# top.net
KiCad netlist of a schematic drawn in Altium Designer
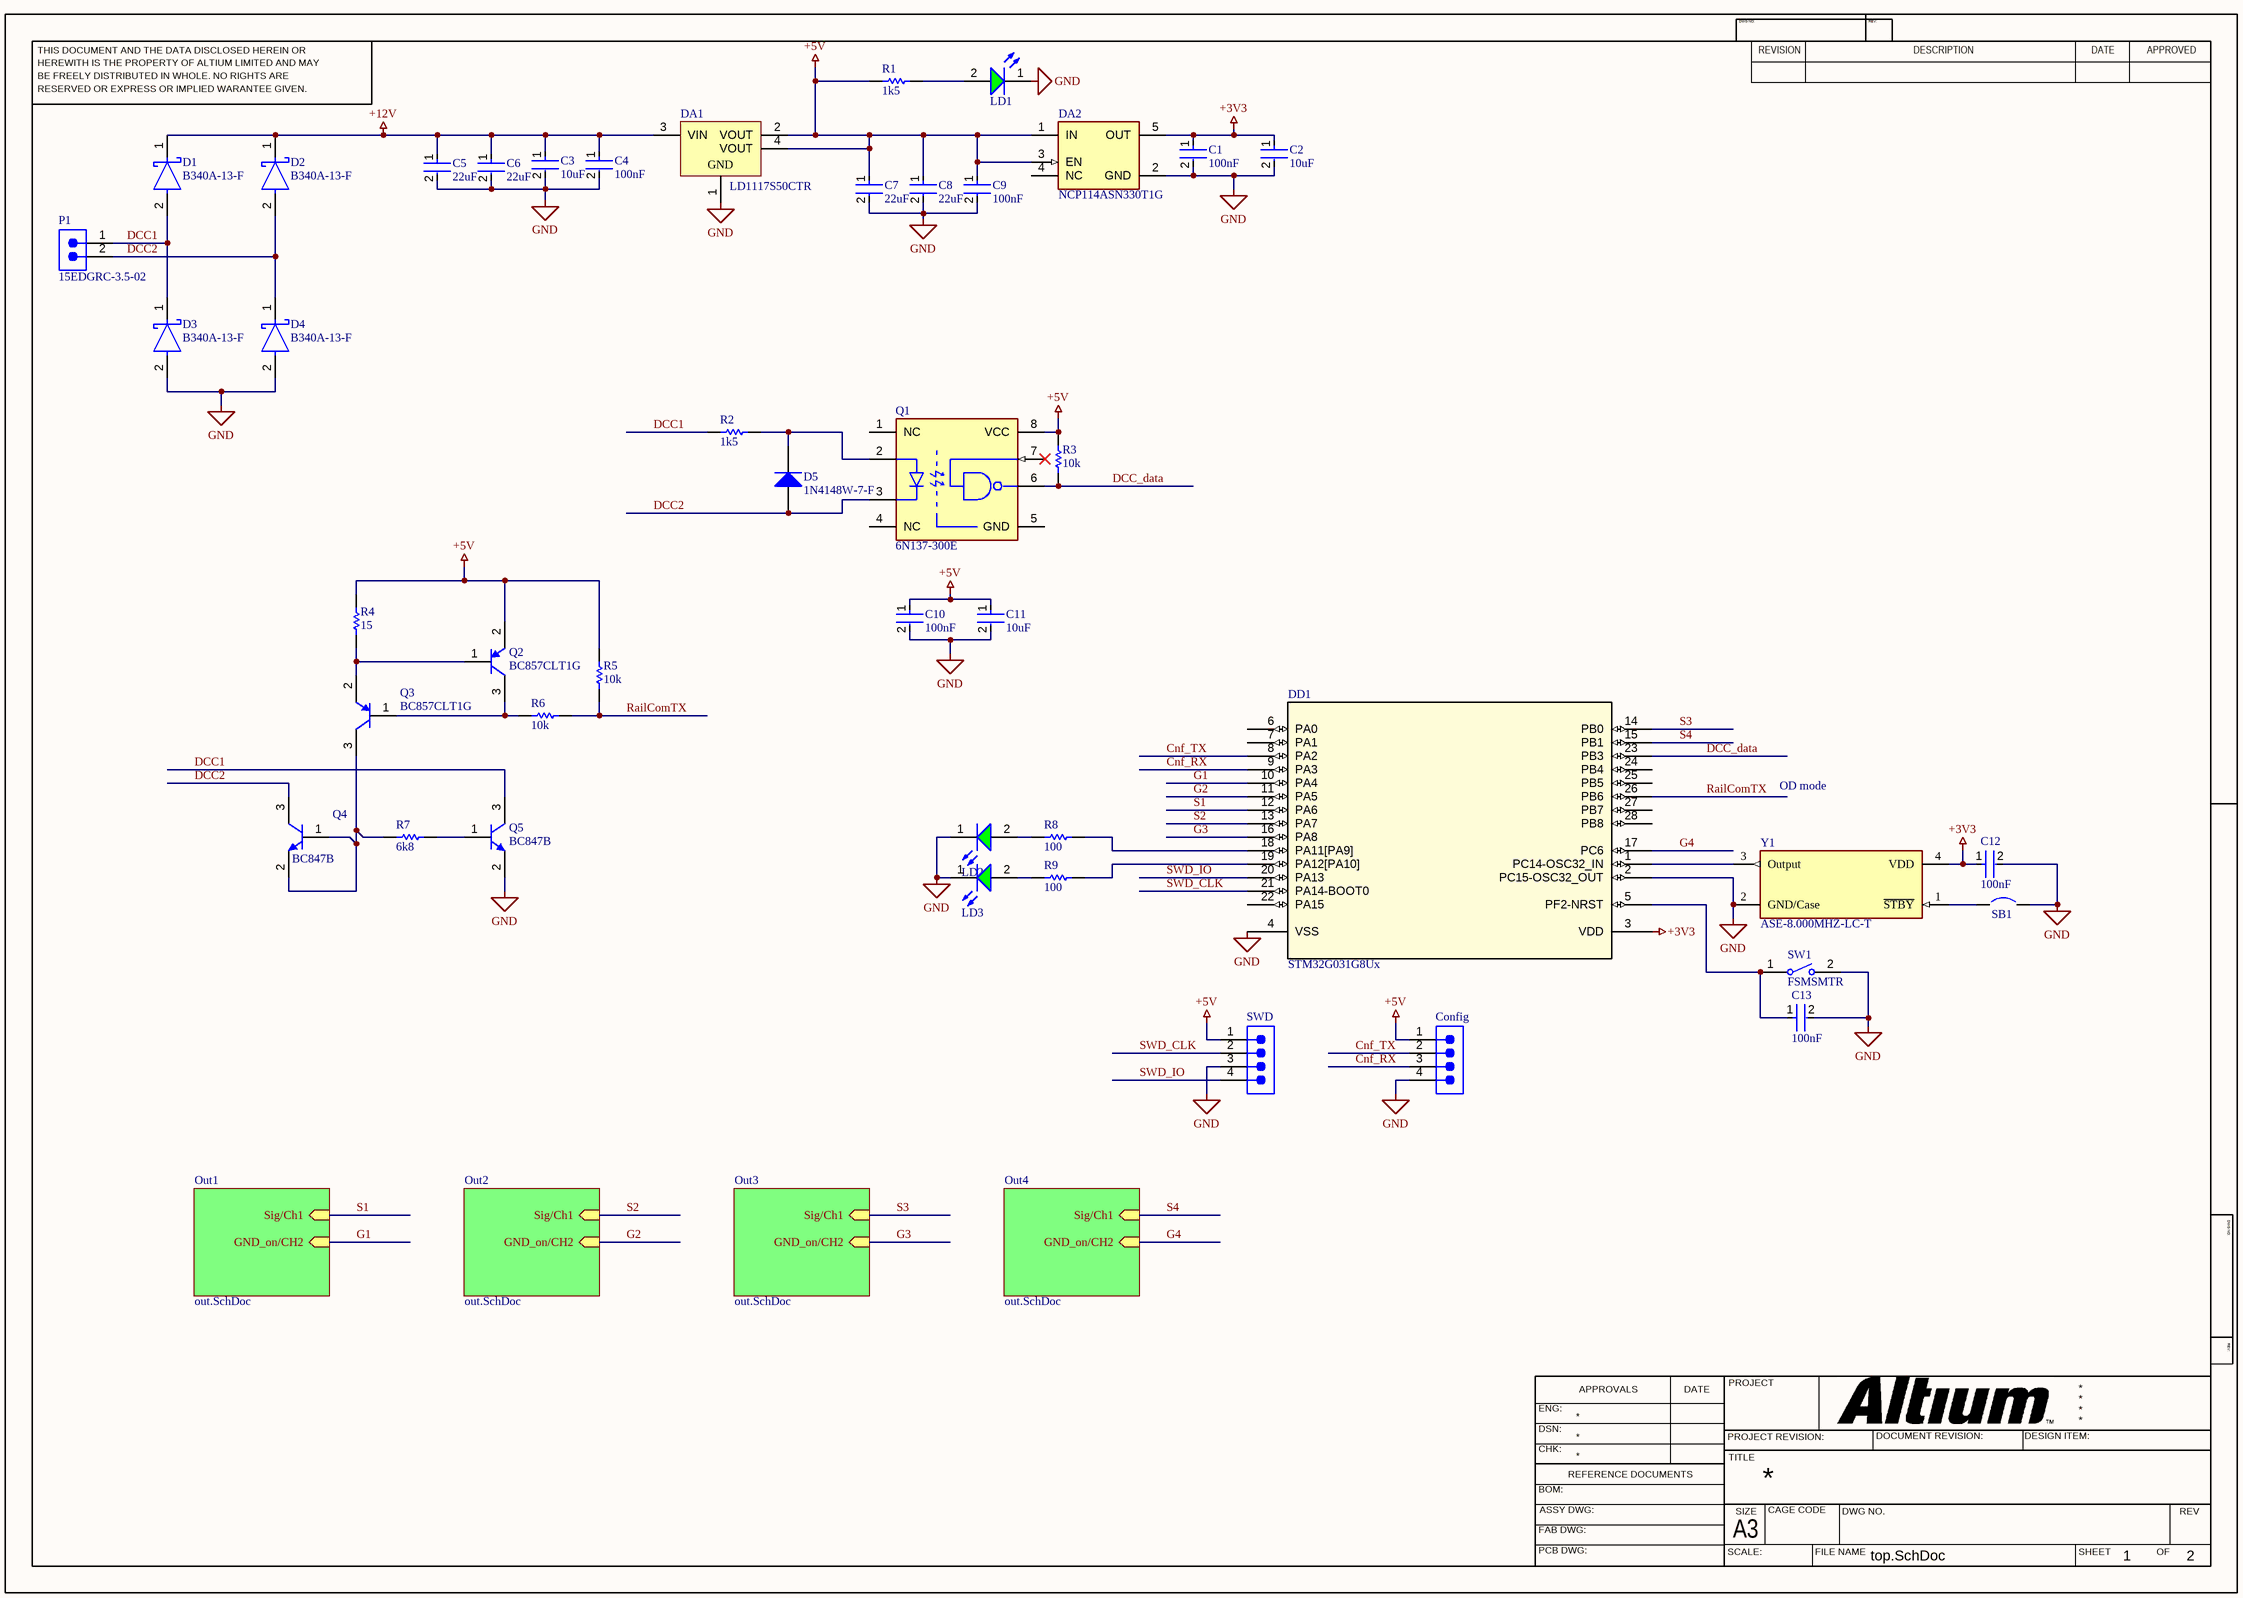
[diagram p0: top.SchDoc]

(export (version "E")
  (design (tool "Eeschema 10.0.6"))
  (components
    (comp (ref "C1")
      (value "CGA3E2X7R1H104K080AA")
      (footprint "FP-CGA3E-0_3-0_1-IPC_C")
      (description "Cap Ceramic 100nF 50V X7R 10% Pad SMD 0603 +125°C Automotive T/R")
      (fields
        (field (name "TOLERANCE") "10%")
        (field (name "CAPACITANCE") "100nF")
        (field (name "VOLTAGE") "50V")
      )
      (libsource (lib "Altium Content Vault") (part "b4654b650e69147ec39a6b967a45e02"))
    )
    (comp (ref "C2")
      (value "GRM188R60J106ME47D")
      (footprint "FP-GRM188-0_1-e0_2_0_55-IPC_C")
      (description "Chip Multilayer Ceramic Capacitors for General Purpose, 0603, 10uF, X5R, 15%, 20%, 6.3V")
      (fields
        (field (name "CAPACITANCE") "10uF")
        (field (name "VOLTAGE") "6.3V")
        (field (name "TOLERANCE") "20%")
      )
      (libsource (lib "Altium Content Vault") (part "02cd4be3c70576c341d710602a673aa"))
    )
    (comp (ref "C3")
      (value "GRM188R60J106ME47D")
      (footprint "FP-GRM188-0_1-e0_2_0_55-IPC_C")
      (description "Chip Multilayer Ceramic Capacitors for General Purpose, 0603, 10uF, X5R, 15%, 20%, 6.3V")
      (fields
        (field (name "CAPACITANCE") "10uF")
        (field (name "VOLTAGE") "6.3V")
        (field (name "TOLERANCE") "20%")
      )
      (libsource (lib "Altium Content Vault") (part "02cd4be3c70576c341d710602a673aa"))
    )
    (comp (ref "C4")
      (value "CGA3E2X7R1H104K080AA")
      (footprint "FP-CGA3E-0_3-0_1-IPC_C")
      (description "Cap Ceramic 100nF 50V X7R 10% Pad SMD 0603 +125°C Automotive T/R")
      (fields
        (field (name "TOLERANCE") "10%")
        (field (name "CAPACITANCE") "100nF")
        (field (name "VOLTAGE") "50V")
      )
      (libsource (lib "Altium Content Vault") (part "b4654b650e69147ec39a6b967a45e02"))
    )
    (comp (ref "C5")
      (value "GRM188R61A226ME15D")
      (footprint "FP-GRM188-0_2-IPC_C")
      (description "Chip Multilayer Ceramic Capacitors for General Purpose, 0603, 22uF, X5R, 15%, 20%, 10V")
      (fields (field (name "TOLERANCE") "20%") (field (name "CAPACITANCE") "22uF"))
      (libsource (lib "Altium Content Vault") (part "11868f565c42a9108669ba33697ecf6"))
    )
    (comp (ref "C6")
      (value "GRM188R61A226ME15D")
      (footprint "FP-GRM188-0_2-IPC_C")
      (description "Chip Multilayer Ceramic Capacitors for General Purpose, 0603, 22uF, X5R, 15%, 20%, 10V")
      (fields (field (name "TOLERANCE") "20%") (field (name "CAPACITANCE") "22uF"))
      (libsource (lib "Altium Content Vault") (part "11868f565c42a9108669ba33697ecf6"))
    )
    (comp (ref "C7")
      (value "GRM188R61A226ME15D")
      (footprint "FP-GRM188-0_2-IPC_C")
      (description "Chip Multilayer Ceramic Capacitors for General Purpose, 0603, 22uF, X5R, 15%, 20%, 10V")
      (fields (field (name "TOLERANCE") "20%") (field (name "CAPACITANCE") "22uF"))
      (libsource (lib "Altium Content Vault") (part "11868f565c42a9108669ba33697ecf6"))
    )
    (comp (ref "C8")
      (value "GRM188R61A226ME15D")
      (footprint "FP-GRM188-0_2-IPC_C")
      (description "Chip Multilayer Ceramic Capacitors for General Purpose, 0603, 22uF, X5R, 15%, 20%, 10V")
      (fields (field (name "TOLERANCE") "20%") (field (name "CAPACITANCE") "22uF"))
      (libsource (lib "Altium Content Vault") (part "11868f565c42a9108669ba33697ecf6"))
    )
    (comp (ref "C9")
      (value "CGA3E2X7R1H104K080AA")
      (footprint "FP-CGA3E-0_3-0_1-IPC_C")
      (description "Cap Ceramic 100nF 50V X7R 10% Pad SMD 0603 +125°C Automotive T/R")
      (fields
        (field (name "TOLERANCE") "10%")
        (field (name "CAPACITANCE") "100nF")
        (field (name "VOLTAGE") "50V")
      )
      (libsource (lib "Altium Content Vault") (part "b4654b650e69147ec39a6b967a45e02"))
    )
    (comp (ref "C10")
      (value "CGA3E2X7R1H104K080AA")
      (footprint "FP-CGA3E-0_3-0_1-IPC_C")
      (description "Cap Ceramic 100nF 50V X7R 10% Pad SMD 0603 +125°C Automotive T/R")
      (fields
        (field (name "TOLERANCE") "10%")
        (field (name "CAPACITANCE") "100nF")
        (field (name "VOLTAGE") "50V")
      )
      (libsource (lib "Altium Content Vault") (part "b4654b650e69147ec39a6b967a45e02"))
    )
    (comp (ref "C11")
      (value "GRM188R60J106ME47D")
      (footprint "FP-GRM188-0_1-e0_2_0_55-IPC_C")
      (description "Chip Multilayer Ceramic Capacitors for General Purpose, 0603, 10uF, X5R, 15%, 20%, 6.3V")
      (fields
        (field (name "CAPACITANCE") "10uF")
        (field (name "VOLTAGE") "6.3V")
        (field (name "TOLERANCE") "20%")
      )
      (libsource (lib "Altium Content Vault") (part "02cd4be3c70576c341d710602a673aa"))
    )
    (comp (ref "C12")
      (value "CGA3E2X7R1H104K080AA")
      (footprint "FP-CGA3E-0_3-0_1-IPC_C")
      (description "Cap Ceramic 100nF 50V X7R 10% Pad SMD 0603 +125°C Automotive T/R")
      (fields
        (field (name "TOLERANCE") "10%")
        (field (name "CAPACITANCE") "100nF")
        (field (name "VOLTAGE") "50V")
      )
      (libsource (lib "Altium Content Vault") (part "b4654b650e69147ec39a6b967a45e02"))
    )
    (comp (ref "C13")
      (value "CGA3E2X7R1H104K080AA")
      (footprint "FP-CGA3E-0_3-0_1-IPC_C")
      (description "Cap Ceramic 100nF 50V X7R 10% Pad SMD 0603 +125°C Automotive T/R")
      (fields
        (field (name "TOLERANCE") "10%")
        (field (name "CAPACITANCE") "100nF")
        (field (name "VOLTAGE") "50V")
      )
      (libsource (lib "Altium Content Vault") (part "b4654b650e69147ec39a6b967a45e02"))
    )
    (comp (ref "Config")
      (value "61300411121")
      (footprint "61300411121")
      (libsource (lib "Altium Content Vault") (part "Header_Male_1R_04P"))
    )
    (comp (ref "D1")
      (value "B340A-13-F")
      (footprint "FP-SMA-MFG")
      (description "DIODE SCHOTTKY 40V 3A SMA")
      (fields (field (name "VOLTAGE") "40V"))
      (libsource (lib "Altium Content Vault") (part "1d6ec82d83fb6aee721767c19dac4b9"))
    )
    (comp (ref "D2")
      (value "B340A-13-F")
      (footprint "FP-SMA-MFG")
      (description "DIODE SCHOTTKY 40V 3A SMA")
      (fields (field (name "VOLTAGE") "40V"))
      (libsource (lib "Altium Content Vault") (part "1d6ec82d83fb6aee721767c19dac4b9"))
    )
    (comp (ref "D3")
      (value "B340A-13-F")
      (footprint "FP-SMA-MFG")
      (description "DIODE SCHOTTKY 40V 3A SMA")
      (fields (field (name "VOLTAGE") "40V"))
      (libsource (lib "Altium Content Vault") (part "1d6ec82d83fb6aee721767c19dac4b9"))
    )
    (comp (ref "D4")
      (value "B340A-13-F")
      (footprint "FP-SMA-MFG")
      (description "DIODE SCHOTTKY 40V 3A SMA")
      (fields (field (name "VOLTAGE") "40V"))
      (libsource (lib "Altium Content Vault") (part "1d6ec82d83fb6aee721767c19dac4b9"))
    )
    (comp (ref "D5")
      (value "1N4148W-7-F")
      (footprint "DIOD-SOD123-2_V")
      (description "Fast Switching Diode, 100 V, 0.15 A, -65 to 150 degC, 2-Pin?SOD123, RoHS, Tape and Reel")
      (fields (field (name "MANUFACTURER") "DiodesIncorporated"))
      (libsource (lib "Altium Content Vault") (part "D-AK-2"))
    )
    (comp (ref "DA1")
      (value "LD1117S50CTR")
      (footprint "SOT-223_N")
      (description "Fixed Low Drop Positive Voltage Regulator, 5V, 4-Pin SOT-223, Tape and Reel")
      (libsource (lib "Altium Content Vault") (part "PM-REG-LD1117-SOT4"))
    )
    (comp (ref "DA2")
      (value "NCP114ASN330T1G")
      (footprint "FP-483-MFG")
      (description "IC REG LINEAR 3.3V 300MA 5TSOP")
      (fields
        (field (name "MANUFACTURER") "ON Semiconductor")
        (field (name "OCTOPART") "https://octopart.com/ncp114asn330t1g-on+semiconductor-74628742")
      )
      (libsource (lib "Altium Content Vault") (part "57814aa37072aacea77ef0fe9350350"))
    )
    (comp (ref "DD1")
      (value "STM32G031G8Ux")
      (footprint "UFQFPN-28")
      (fields
        (field (name "MANUFACTURER_PART_NUMBER") "stm32g0_ufqfpn28_t1")
        (field (name "COPYRIGHT") "Copyright (C) 2016 Accelerated Designs. All rights reserved")
      )
      (libsource (lib "ST Microelectronics STM32 G0") (part "STM32G031G8Ux"))
    )
    (comp (ref "LD1")
      (value "150060VS75000")
      (footprint "WL-SMCW_0603_150060xx75000")
      (description "WURTH ELEKTRONIK - 150060VS75000 - LED, Green, SMD, 0603, 30 mA, 2 V, 570 nm")
      (libsource (lib "Altium Content Vault") (part "LED_Green_2A-1K"))
    )
    (comp (ref "LD2")
      (value "150060VS75000")
      (footprint "WL-SMCW_0603_150060xx75000")
      (description "WURTH ELEKTRONIK - 150060VS75000 - LED, Green, SMD, 0603, 30 mA, 2 V, 570 nm")
      (libsource (lib "Altium Content Vault") (part "LED_Green_2A-1K"))
    )
    (comp (ref "LD3")
      (value "150060VS75000")
      (footprint "WL-SMCW_0603_150060xx75000")
      (description "WURTH ELEKTRONIK - 150060VS75000 - LED, Green, SMD, 0603, 30 mA, 2 V, 570 nm")
      (libsource (lib "Altium Content Vault") (part "LED_Green_2A-1K"))
    )
    (comp (ref "P1")
      (value "15EDGRC-3.5-02")
      (footprint "691305140002")
      (libsource (lib "Altium Content Vault") (part "TBL - 1R - 02P - Male"))
    )
    (comp (ref "Q1")
      (value "6N137-300E")
      (footprint "FP-6N137-300E-MFG")
      (description "OPTOISO 3.75KV OPN COLL 8DIP GW")
      (fields
        (field (name "MANUFACTURER") "Broadcom")
        (field (name "OCTOPART") "https://octopart.com/6n137-300e-broadcom-71125550")
      )
      (libsource (lib "Altium Content Vault") (part "086db94909ba3b4bba0ec19532872cc"))
    )
    (comp (ref "Q2")
      (value "BC857CLT1G")
      (footprint "ONSC-SOT-23-3-318-08_V")
      (description "General Purpose Transistor, PNP Silicon, 3-Pin SOT-23, Pb-Free, Tape and Reel")
      (fields (field (name "MANUFACTURER") "On Semiconductor"))
      (libsource (lib "Altium Content Vault") (part "ONSC-PNP-B1E2C3-3"))
    )
    (comp (ref "Q3")
      (value "BC857CLT1G")
      (footprint "ONSC-SOT-23-3-318-08_V")
      (description "General Purpose Transistor, PNP Silicon, 3-Pin SOT-23, Pb-Free, Tape and Reel")
      (fields (field (name "MANUFACTURER") "On Semiconductor"))
      (libsource (lib "Altium Content Vault") (part "ONSC-PNP-B1E2C3-3"))
    )
    (comp (ref "Q4")
      (value "BC847B")
      (footprint "INF-SOT23_M")
      (description "NPN Silicon AF Transistor, 45 V VCEO, 100 mA IC, SOT23, Reel, Green")
      (fields (field (name "MANUFACTURER") "Infineon"))
      (libsource (lib "Altium Content Vault") (part "INF-BJTNPN-BEC-3"))
    )
    (comp (ref "Q5")
      (value "BC847B")
      (footprint "INF-SOT23_M")
      (description "NPN Silicon AF Transistor, 45 V VCEO, 100 mA IC, SOT23, Reel, Green")
      (fields (field (name "MANUFACTURER") "Infineon"))
      (libsource (lib "Altium Content Vault") (part "INF-BJTNPN-BEC-3"))
    )
    (comp (ref "R1")
      (value "1k5")
      (footprint "RESC1608X55X25ML10T15")
      (description "Chip Resistor, 1.5 KOhm, +/- 1%, 0.1 W, -55 to 155 degC, 0603 (1608 Metric), RoHS, Tape and Reel")
      (fields (field (name "TOLERANCE") "1%") (field (name "MANUFACTURER") "Yageo"))
      (libsource (lib "Altium Content Vault") (part "RES-2"))
    )
    (comp (ref "R2")
      (value "1k5")
      (footprint "RESC1608X55X25ML10T15")
      (description "Chip Resistor, 1.5 KOhm, +/- 1%, 0.1 W, -55 to 155 degC, 0603 (1608 Metric), RoHS, Tape and Reel")
      (fields (field (name "TOLERANCE") "1%") (field (name "MANUFACTURER") "Yageo"))
      (libsource (lib "Altium Content Vault") (part "RES-2"))
    )
    (comp (ref "R3")
      (value "10k")
      (footprint "RESC1609X55X30NL15T15")
      (description "Chip Resistor, 10 KOhm, +/- 1%, 0.1 W, -55 to 155 degC, 0603 (1608 Metric), RoHS, Tape and Reel")
      (fields (field (name "TOLERANCE") "1%") (field (name "MANUFACTURER") "Panasonic"))
      (libsource (lib "Altium Content Vault") (part "RES-2"))
    )
    (comp (ref "R4")
      (value "15")
      (footprint "RESC1608X55X30NL15T15")
      (fields (field (name "PART NUMBER") "ERJ-3EKF1502V") (field (name "MANUFACTURER") "Panasonic"))
      (libsource (lib "Altium Content Vault") (part "RES"))
    )
    (comp (ref "R5")
      (value "10k")
      (footprint "RESC1609X55X30NL15T15")
      (description "Chip Resistor, 10 KOhm, +/- 1%, 0.1 W, -55 to 155 degC, 0603 (1608 Metric), RoHS, Tape and Reel")
      (fields (field (name "TOLERANCE") "1%") (field (name "MANUFACTURER") "Panasonic"))
      (libsource (lib "Altium Content Vault") (part "RES-2"))
    )
    (comp (ref "R6")
      (value "10k")
      (footprint "RESC1609X55X30NL15T15")
      (description "Chip Resistor, 10 KOhm, +/- 1%, 0.1 W, -55 to 155 degC, 0603 (1608 Metric), RoHS, Tape and Reel")
      (fields (field (name "TOLERANCE") "1%") (field (name "MANUFACTURER") "Panasonic"))
      (libsource (lib "Altium Content Vault") (part "RES-2"))
    )
    (comp (ref "R7")
      (value "6k8")
      (footprint "RESC1608X55X25NL10T15")
      (description "Chip Resistor, 6.8 KOhm, +/- 1%, 100 mW, -55 to 155 degC, 0603 (1608 Metric), RoHS, Tape and Reel")
      (fields (field (name "Comment") "RC0603FR-076K8L"))
      (libsource (lib "Altium Content Vault") (part "RES-2"))
    )
    (comp (ref "R8")
      (value "100")
      (footprint "RESC1608X55X30NL15T15")
      (fields (field (name "PART NUMBER") "ERJ-3EKF1003V") (field (name "MANUFACTURER") "Panasonic"))
      (libsource (lib "Altium Content Vault") (part "RES"))
    )
    (comp (ref "R9")
      (value "100")
      (footprint "RESC1608X55X30NL15T15")
      (fields (field (name "PART NUMBER") "ERJ-3EKF1003V") (field (name "MANUFACTURER") "Panasonic"))
      (libsource (lib "Altium Content Vault") (part "RES"))
    )
    (comp (ref "SB1")
      (value "~")
      (footprint "JP_SMD")
      (description "Circuit Breaker")
      (fields (field (name "PUBLISHER") "Altium Limited"))
      (libsource (lib "test_adc") (part "Circuit Breaker"))
    )
    (comp (ref "SW1")
      (value "FSMSMTR")
      (footprint "TECO-FSMSMTR_V")
      (description "FSMSM Push Button Switch, 50 mA, -35 to 85 degC, 2-Pin SMD, RoHS, Tape and Reel")
      (fields (field (name "MANUFACTURER") "TE Connectivity"))
      (libsource (lib "Altium Content Vault") (part "SW-SPST-2_C"))
    )
    (comp (ref "SWD")
      (value "61300411121")
      (footprint "61300411121")
      (libsource (lib "Altium Content Vault") (part "Header_Male_1R_04P"))
    )
    (comp (ref "Y1")
      (value "ASE-8.000MHZ-LC-T")
      (footprint "FP-ASE-MFG")
      (description "XTAL Oscillator 8MHz ±50ppm CMOS 3.3V 4-SMD 3.2mm x 2.5mm")
      (libsource (lib "Altium Content Vault") (part "61a724e6190563596ac712fef61ad37"))
    )
  )
  (nets
    (net (code "1") (name "+3V3") (class "Default")
      (node (ref "C1") (pin "1") (pinfunction "1_1") (pintype "passive"))
      (node (ref "C12") (pin "1") (pinfunction "1_1") (pintype "passive"))
      (node (ref "C2") (pin "1") (pinfunction "1_1") (pintype "passive"))
      (node (ref "DA2") (pin "5") (pinfunction "OUT_5") (pintype "power_in"))
      (node (ref "DD1") (pin "3") (pinfunction "VDD_3") (pintype "power_in"))
      (node (ref "Y1") (pin "4") (pinfunction "VDD_4") (pintype "power_in"))
    )
    (net (code "2") (name "+5V") (class "Default")
      (node (ref "C10") (pin "1") (pinfunction "1_1") (pintype "passive"))
      (node (ref "C11") (pin "1") (pinfunction "1_1") (pintype "passive"))
      (node (ref "C7") (pin "1") (pinfunction "1_1") (pintype "passive"))
      (node (ref "C8") (pin "1") (pinfunction "1_1") (pintype "passive"))
      (node (ref "C9") (pin "1") (pinfunction "1_1") (pintype "passive"))
      (node (ref "Config") (pin "1") (pinfunction "1_1") (pintype "passive"))
      (node (ref "DA1") (pin "2") (pinfunction "VOUT_2") (pintype "power_in"))
      (node (ref "DA1") (pin "4") (pinfunction "VOUT_4") (pintype "power_in"))
      (node (ref "DA2") (pin "1") (pinfunction "IN_1") (pintype "power_in"))
      (node (ref "DA2") (pin "3") (pinfunction "EN_3") (pintype "input"))
      (node (ref "Q1") (pin "8") (pinfunction "VCC_8") (pintype "power_in"))
      (node (ref "Q2") (pin "2") (pinfunction "E_2") (pintype "passive"))
      (node (ref "R1") (pin "1") (pinfunction "1_1") (pintype "passive"))
      (node (ref "R3") (pin "1") (pinfunction "1_1") (pintype "passive"))
      (node (ref "R4") (pin "2") (pinfunction "2_2") (pintype "passive"))
      (node (ref "R5") (pin "1") (pinfunction "1_1") (pintype "passive"))
      (node (ref "SWD") (pin "1") (pinfunction "1_1") (pintype "passive"))
    )
    (net (code "3") (name "+12V") (class "Default")
      (node (ref "C3") (pin "1") (pinfunction "1_1") (pintype "passive"))
      (node (ref "C4") (pin "1") (pinfunction "1_1") (pintype "passive"))
      (node (ref "C5") (pin "1") (pinfunction "1_1") (pintype "passive"))
      (node (ref "C6") (pin "1") (pinfunction "1_1") (pintype "passive"))
      (node (ref "D1") (pin "1") (pinfunction "C_1") (pintype "passive"))
      (node (ref "D2") (pin "1") (pinfunction "C_1") (pintype "passive"))
      (node (ref "DA1") (pin "3") (pinfunction "VIN_3") (pintype "power_in"))
    )
    (net (code "4") (name "/Cnf_RX") (class "Default")
      (node (ref "Config") (pin "3") (pinfunction "3_3") (pintype "passive"))
      (node (ref "DD1") (pin "9") (pinfunction "PA3_9") (pintype "bidirectional"))
    )
    (net (code "5") (name "/Cnf_TX") (class "Default")
      (node (ref "Config") (pin "2") (pinfunction "2_2") (pintype "passive"))
      (node (ref "DD1") (pin "8") (pinfunction "PA2_8") (pintype "bidirectional"))
    )
    (net (code "6") (name "/DCC1") (class "Default")
      (node (ref "D1") (pin "2") (pinfunction "A_2") (pintype "passive"))
      (node (ref "D3") (pin "1") (pinfunction "C_1") (pintype "passive"))
      (node (ref "P1") (pin "1") (pinfunction "1_1") (pintype "passive"))
      (node (ref "Q5") (pin "3") (pinfunction "C_3") (pintype "passive"))
      (node (ref "R2") (pin "1") (pinfunction "1_1") (pintype "passive"))
    )
    (net (code "7") (name "/DCC2") (class "Default")
      (node (ref "D2") (pin "2") (pinfunction "A_2") (pintype "passive"))
      (node (ref "D4") (pin "1") (pinfunction "C_1") (pintype "passive"))
      (node (ref "D5") (pin "1") (pinfunction "A_1") (pintype "passive"))
      (node (ref "P1") (pin "2") (pinfunction "2_2") (pintype "passive"))
      (node (ref "Q1") (pin "3") (pinfunction "C_3") (pintype "passive"))
      (node (ref "Q4") (pin "3") (pinfunction "C_3") (pintype "passive"))
    )
    (net (code "8") (name "/DCC_data") (class "Default")
      (node (ref "DD1") (pin "23") (pinfunction "PB3_23") (pintype "bidirectional"))
      (node (ref "Q1") (pin "6") (pinfunction "VO_6") (pintype "open_collector"))
      (node (ref "R3") (pin "2") (pinfunction "2_2") (pintype "passive"))
    )
    (net (code "9") (name "/G1") (class "Default")
      (node (ref "DD1") (pin "10") (pinfunction "PA4_10") (pintype "bidirectional"))
    )
    (net (code "10") (name "/G2") (class "Default")
      (node (ref "DD1") (pin "11") (pinfunction "PA5_11") (pintype "bidirectional"))
    )
    (net (code "11") (name "/G3") (class "Default")
      (node (ref "DD1") (pin "16") (pinfunction "PA8_16") (pintype "bidirectional"))
    )
    (net (code "12") (name "/G4") (class "Default")
      (node (ref "DD1") (pin "17") (pinfunction "PC6_17") (pintype "bidirectional"))
    )
    (net (code "13") (name "/RailComTX") (class "Default")
      (node (ref "DD1") (pin "26") (pinfunction "PB6_26") (pintype "bidirectional"))
      (node (ref "R5") (pin "2") (pinfunction "2_2") (pintype "passive"))
      (node (ref "R6") (pin "1") (pinfunction "1_1") (pintype "passive"))
    )
    (net (code "14") (name "/S1") (class "Default")
      (node (ref "DD1") (pin "12") (pinfunction "PA6_12") (pintype "bidirectional"))
    )
    (net (code "15") (name "/S2") (class "Default")
      (node (ref "DD1") (pin "13") (pinfunction "PA7_13") (pintype "bidirectional"))
    )
    (net (code "16") (name "/S3") (class "Default")
      (node (ref "DD1") (pin "14") (pinfunction "PB0_14") (pintype "bidirectional"))
    )
    (net (code "17") (name "/S4") (class "Default")
      (node (ref "DD1") (pin "15") (pinfunction "PB1_15") (pintype "bidirectional"))
    )
    (net (code "18") (name "/SWD_CLK") (class "Default")
      (node (ref "DD1") (pin "21") (pinfunction "PA14-BOOT0_21") (pintype "bidirectional"))
      (node (ref "SWD") (pin "2") (pinfunction "2_2") (pintype "passive"))
    )
    (net (code "19") (name "/SWD_IO") (class "Default")
      (node (ref "DD1") (pin "20") (pinfunction "PA13_20") (pintype "bidirectional"))
      (node (ref "SWD") (pin "4") (pinfunction "4_4") (pintype "passive"))
    )
    (net (code "20") (name "GND") (class "Default")
      (node (ref "C1") (pin "2") (pinfunction "2_2") (pintype "passive"))
      (node (ref "C10") (pin "2") (pinfunction "2_2") (pintype "passive"))
      (node (ref "C11") (pin "2") (pinfunction "2_2") (pintype "passive"))
      (node (ref "C12") (pin "2") (pinfunction "2_2") (pintype "passive"))
      (node (ref "C13") (pin "2") (pinfunction "2_2") (pintype "passive"))
      (node (ref "C2") (pin "2") (pinfunction "2_2") (pintype "passive"))
      (node (ref "C3") (pin "2") (pinfunction "2_2") (pintype "passive"))
      (node (ref "C4") (pin "2") (pinfunction "2_2") (pintype "passive"))
      (node (ref "C5") (pin "2") (pinfunction "2_2") (pintype "passive"))
      (node (ref "C6") (pin "2") (pinfunction "2_2") (pintype "passive"))
      (node (ref "C7") (pin "2") (pinfunction "2_2") (pintype "passive"))
      (node (ref "C8") (pin "2") (pinfunction "2_2") (pintype "passive"))
      (node (ref "C9") (pin "2") (pinfunction "2_2") (pintype "passive"))
      (node (ref "Config") (pin "4") (pinfunction "4_4") (pintype "passive"))
      (node (ref "D3") (pin "2") (pinfunction "A_2") (pintype "passive"))
      (node (ref "D4") (pin "2") (pinfunction "A_2") (pintype "passive"))
      (node (ref "DA1") (pin "1") (pinfunction "GND_1") (pintype "power_in"))
      (node (ref "DA2") (pin "2") (pinfunction "GND_2") (pintype "power_in"))
      (node (ref "DD1") (pin "2") (pinfunction "PC15-OSC32_OUT_2") (pintype "bidirectional"))
      (node (ref "DD1") (pin "4") (pinfunction "VSS_4") (pintype "power_in"))
      (node (ref "LD1") (pin "1") (pinfunction "K_1") (pintype "passive"))
      (node (ref "LD2") (pin "1") (pinfunction "K_1") (pintype "passive"))
      (node (ref "LD3") (pin "1") (pinfunction "K_1") (pintype "passive"))
      (node (ref "Q5") (pin "2") (pinfunction "E_2") (pintype "passive"))
      (node (ref "SB1") (pin "2") (pinfunction "2_2") (pintype "passive"))
      (node (ref "SW1") (pin "2") (pinfunction "2_2") (pintype "passive"))
      (node (ref "SWD") (pin "3") (pinfunction "3_3") (pintype "passive"))
      (node (ref "Y1") (pin "2") (pinfunction "GND/Case_2") (pintype "power_in"))
    )
    (net (code "21") (name "Net-(D5-K)") (class "Default")
      (node (ref "D5") (pin "2") (pinfunction "K_2") (pintype "passive"))
      (node (ref "Q1") (pin "2") (pinfunction "A_2") (pintype "passive"))
      (node (ref "R2") (pin "2") (pinfunction "2_2") (pintype "passive"))
    )
    (net (code "22") (name "Net-(DD1-PA11[PA9])") (class "Default")
      (node (ref "DD1") (pin "18") (pinfunction "PA11[PA9]_18") (pintype "bidirectional"))
      (node (ref "R8") (pin "1") (pinfunction "1_1") (pintype "passive"))
    )
    (net (code "23") (name "Net-(DD1-PA12[PA10])") (class "Default")
      (node (ref "DD1") (pin "19") (pinfunction "PA12[PA10]_19") (pintype "bidirectional"))
      (node (ref "R9") (pin "1") (pinfunction "1_1") (pintype "passive"))
    )
    (net (code "24") (name "Net-(DD1-PC14-OSC32_IN)") (class "Default")
      (node (ref "DD1") (pin "1") (pinfunction "PC14-OSC32_IN_1") (pintype "bidirectional"))
      (node (ref "Y1") (pin "3") (pinfunction "Output_3") (pintype "output"))
    )
    (net (code "25") (name "Net-(DD1-PF2-NRST)") (class "Default")
      (node (ref "C13") (pin "1") (pinfunction "1_1") (pintype "passive"))
      (node (ref "DD1") (pin "5") (pinfunction "PF2-NRST_5") (pintype "bidirectional"))
      (node (ref "SW1") (pin "1") (pinfunction "1_1") (pintype "passive"))
    )
    (net (code "26") (name "Net-(LD1-A)") (class "Default")
      (node (ref "LD1") (pin "2") (pinfunction "A_2") (pintype "passive"))
      (node (ref "R1") (pin "2") (pinfunction "2_2") (pintype "passive"))
    )
    (net (code "27") (name "Net-(LD2-A)") (class "Default")
      (node (ref "LD2") (pin "2") (pinfunction "A_2") (pintype "passive"))
      (node (ref "R8") (pin "2") (pinfunction "2_2") (pintype "passive"))
    )
    (net (code "28") (name "Net-(LD3-A)") (class "Default")
      (node (ref "LD3") (pin "2") (pinfunction "A_2") (pintype "passive"))
      (node (ref "R9") (pin "2") (pinfunction "2_2") (pintype "passive"))
    )
    (net (code "29") (name "Net-(Q2-B)") (class "Default")
      (node (ref "Q2") (pin "1") (pinfunction "B_1") (pintype "passive"))
      (node (ref "Q3") (pin "2") (pinfunction "E_2") (pintype "passive"))
      (node (ref "R4") (pin "1") (pinfunction "1_1") (pintype "passive"))
    )
    (net (code "30") (name "Net-(Q2-C)") (class "Default")
      (node (ref "Q2") (pin "3") (pinfunction "C_3") (pintype "passive"))
      (node (ref "Q3") (pin "1") (pinfunction "B_1") (pintype "passive"))
      (node (ref "R6") (pin "2") (pinfunction "2_2") (pintype "passive"))
    )
    (net (code "31") (name "Net-(Q3-C)") (class "Default")
      (node (ref "Q3") (pin "3") (pinfunction "C_3") (pintype "passive"))
      (node (ref "Q4") (pin "1") (pinfunction "B_1") (pintype "passive"))
      (node (ref "Q4") (pin "2") (pinfunction "E_2") (pintype "passive"))
      (node (ref "R7") (pin "1") (pinfunction "1_1") (pintype "passive"))
    )
    (net (code "32") (name "Net-(Q5-B)") (class "Default")
      (node (ref "Q5") (pin "1") (pinfunction "B_1") (pintype "passive"))
      (node (ref "R7") (pin "2") (pinfunction "2_2") (pintype "passive"))
    )
    (net (code "33") (name "Net-(Y1-~{STBY})") (class "Default")
      (node (ref "SB1") (pin "1") (pinfunction "1_1") (pintype "passive"))
      (node (ref "Y1") (pin "1") (pinfunction "~{STBY}_1") (pintype "input"))
    )
    (net (code "34") (name "unconnected-(DA2-NC-Pad4)") (class "Default")
      (node (ref "DA2") (pin "4") (pinfunction "NC_4") (pintype "passive"))
    )
    (net (code "35") (name "unconnected-(DD1-PA0-Pad6)") (class "Default")
      (node (ref "DD1") (pin "6") (pinfunction "PA0_6") (pintype "bidirectional"))
    )
    (net (code "36") (name "unconnected-(DD1-PA1-Pad7)") (class "Default")
      (node (ref "DD1") (pin "7") (pinfunction "PA1_7") (pintype "bidirectional"))
    )
    (net (code "37") (name "unconnected-(DD1-PA15-Pad22)") (class "Default")
      (node (ref "DD1") (pin "22") (pinfunction "PA15_22") (pintype "bidirectional"))
    )
    (net (code "38") (name "unconnected-(DD1-PB4-Pad24)") (class "Default")
      (node (ref "DD1") (pin "24") (pinfunction "PB4_24") (pintype "bidirectional"))
    )
    (net (code "39") (name "unconnected-(DD1-PB5-Pad25)") (class "Default")
      (node (ref "DD1") (pin "25") (pinfunction "PB5_25") (pintype "bidirectional"))
    )
    (net (code "40") (name "unconnected-(DD1-PB7-Pad27)") (class "Default")
      (node (ref "DD1") (pin "27") (pinfunction "PB7_27") (pintype "bidirectional"))
    )
    (net (code "41") (name "unconnected-(DD1-PB8-Pad28)") (class "Default")
      (node (ref "DD1") (pin "28") (pinfunction "PB8_28") (pintype "bidirectional"))
    )
    (net (code "42") (name "unconnected-(Q1-GND-Pad5)") (class "Default")
      (node (ref "Q1") (pin "5") (pinfunction "GND_5") (pintype "power_in"))
    )
    (net (code "43") (name "unconnected-(Q1-NC-Pad1)") (class "Default")
      (node (ref "Q1") (pin "1") (pinfunction "NC_1") (pintype "passive"))
    )
    (net (code "44") (name "unconnected-(Q1-NC-Pad4)") (class "Default")
      (node (ref "Q1") (pin "4") (pinfunction "NC_4") (pintype "passive"))
    )
    (net (code "45") (name "unconnected-(Q1-VE-Pad7)") (class "Default")
      (node (ref "Q1") (pin "7") (pinfunction "VE_7") (pintype "input+no_connect"))
    )
  )
)
